# traduttore.net
KiCad netlist of a schematic drawn in EAGLE
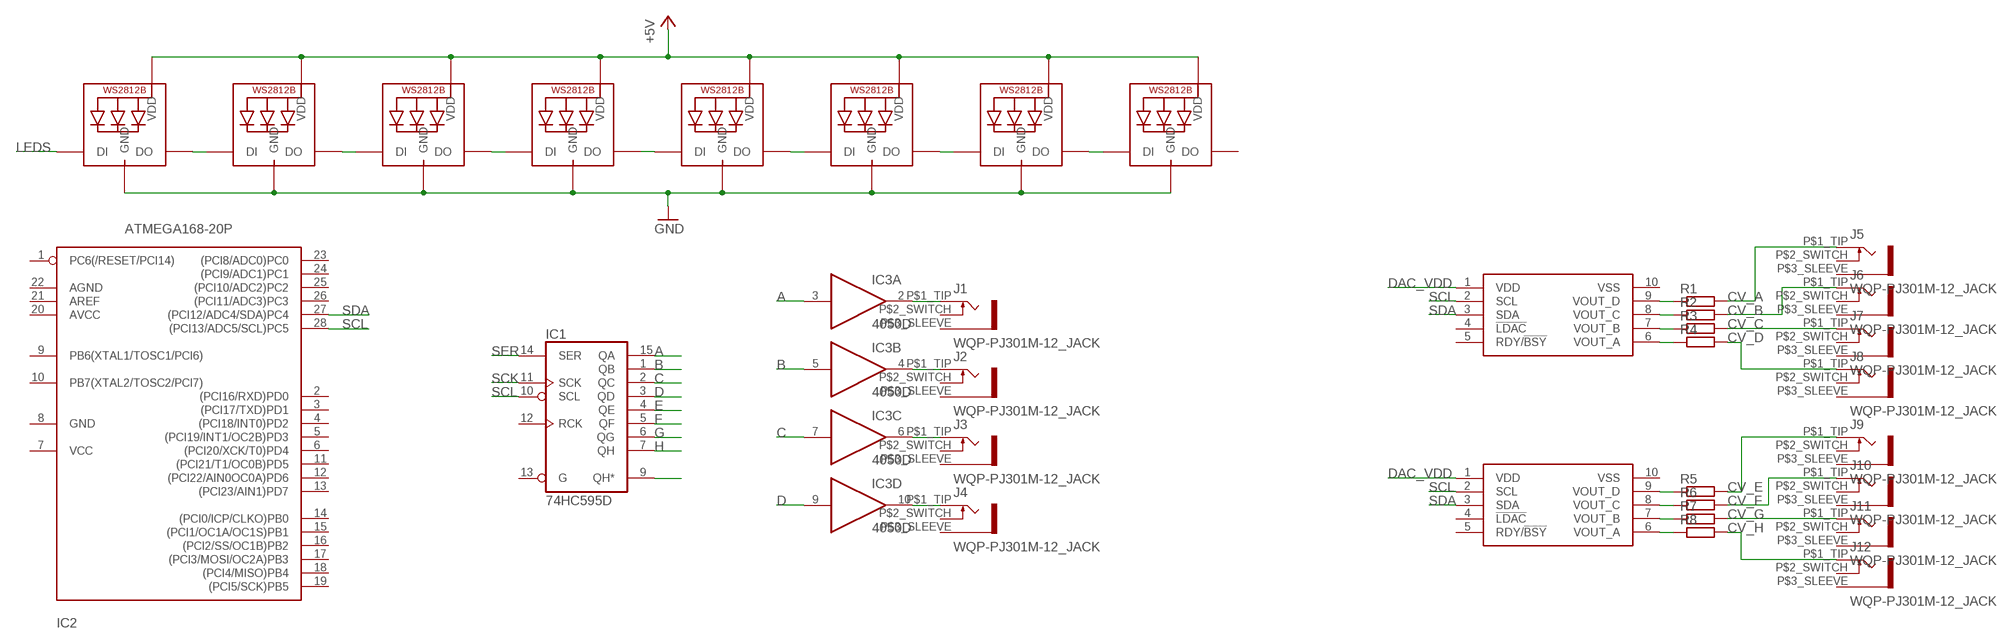
[diagram p0: schematic, sheet 1]

(export (version "E")
  (design (tool "Eeschema 10.0.6"))
  (components
    (comp (ref "IC1")
      (value "74HC595D")
      (footprint "eagle-import:SO16")
      (libsource (lib "eagle-import") (part "74595DHC"))
    )
    (comp (ref "IC2")
      (value "ATMEGA168-20P")
      (footprint "eagle-import:DIL28-3")
      (libsource (lib "eagle-import") (part "ATMEGA168P-20"))
    )
    (comp (ref "IC3")
      (value "4050D")
      (footprint "eagle-import:SO16")
      (libsource (lib "eagle-import") (part "4050D"))
    )
    (comp (ref "J1")
      (value "WQP-PJ301M-12_JACK")
      (footprint "eagle-import:WQP-PJ301M-12_JACK")
      (libsource (lib "eagle-import") (part "WQP-PJ301M-12_JACK"))
    )
    (comp (ref "J2")
      (value "WQP-PJ301M-12_JACK")
      (footprint "eagle-import:WQP-PJ301M-12_JACK")
      (libsource (lib "eagle-import") (part "WQP-PJ301M-12_JACK"))
    )
    (comp (ref "J3")
      (value "WQP-PJ301M-12_JACK")
      (footprint "eagle-import:WQP-PJ301M-12_JACK")
      (libsource (lib "eagle-import") (part "WQP-PJ301M-12_JACK"))
    )
    (comp (ref "J4")
      (value "WQP-PJ301M-12_JACK")
      (footprint "eagle-import:WQP-PJ301M-12_JACK")
      (libsource (lib "eagle-import") (part "WQP-PJ301M-12_JACK"))
    )
    (comp (ref "J5")
      (value "WQP-PJ301M-12_JACK")
      (footprint "eagle-import:WQP-PJ301M-12_JACK")
      (libsource (lib "eagle-import") (part "WQP-PJ301M-12_JACK"))
    )
    (comp (ref "J6")
      (value "WQP-PJ301M-12_JACK")
      (footprint "eagle-import:WQP-PJ301M-12_JACK")
      (libsource (lib "eagle-import") (part "WQP-PJ301M-12_JACK"))
    )
    (comp (ref "J7")
      (value "WQP-PJ301M-12_JACK")
      (footprint "eagle-import:WQP-PJ301M-12_JACK")
      (libsource (lib "eagle-import") (part "WQP-PJ301M-12_JACK"))
    )
    (comp (ref "J8")
      (value "WQP-PJ301M-12_JACK")
      (footprint "eagle-import:WQP-PJ301M-12_JACK")
      (libsource (lib "eagle-import") (part "WQP-PJ301M-12_JACK"))
    )
    (comp (ref "J9")
      (value "WQP-PJ301M-12_JACK")
      (footprint "eagle-import:WQP-PJ301M-12_JACK")
      (libsource (lib "eagle-import") (part "WQP-PJ301M-12_JACK"))
    )
    (comp (ref "J10")
      (value "WQP-PJ301M-12_JACK")
      (footprint "eagle-import:WQP-PJ301M-12_JACK")
      (libsource (lib "eagle-import") (part "WQP-PJ301M-12_JACK"))
    )
    (comp (ref "J11")
      (value "WQP-PJ301M-12_JACK")
      (footprint "eagle-import:WQP-PJ301M-12_JACK")
      (libsource (lib "eagle-import") (part "WQP-PJ301M-12_JACK"))
    )
    (comp (ref "J12")
      (value "WQP-PJ301M-12_JACK")
      (footprint "eagle-import:WQP-PJ301M-12_JACK")
      (libsource (lib "eagle-import") (part "WQP-PJ301M-12_JACK"))
    )
    (comp (ref "LED1")
      (value "WS2812B5050")
      (footprint "eagle-import:WS2812B")
      (libsource (lib "eagle-import") (part "WS2812B5050"))
    )
    (comp (ref "LED2")
      (value "WS2812B5050")
      (footprint "eagle-import:WS2812B")
      (libsource (lib "eagle-import") (part "WS2812B5050"))
    )
    (comp (ref "LED3")
      (value "WS2812B5050")
      (footprint "eagle-import:WS2812B")
      (libsource (lib "eagle-import") (part "WS2812B5050"))
    )
    (comp (ref "LED4")
      (value "WS2812B5050")
      (footprint "eagle-import:WS2812B")
      (libsource (lib "eagle-import") (part "WS2812B5050"))
    )
    (comp (ref "LED5")
      (value "WS2812B5050")
      (footprint "eagle-import:WS2812B")
      (libsource (lib "eagle-import") (part "WS2812B5050"))
    )
    (comp (ref "LED6")
      (value "WS2812B5050")
      (footprint "eagle-import:WS2812B")
      (libsource (lib "eagle-import") (part "WS2812B5050"))
    )
    (comp (ref "LED7")
      (value "WS2812B5050")
      (footprint "eagle-import:WS2812B")
      (libsource (lib "eagle-import") (part "WS2812B5050"))
    )
    (comp (ref "LED8")
      (value "WS2812B5050")
      (footprint "eagle-import:WS2812B")
      (libsource (lib "eagle-import") (part "WS2812B5050"))
    )
    (comp (ref "R1")
      (value "R-EU_R0805")
      (footprint "eagle-import:R0805")
      (libsource (lib "eagle-import") (part "R-EU_R0805"))
    )
    (comp (ref "R2")
      (value "R-EU_R0805")
      (footprint "eagle-import:R0805")
      (libsource (lib "eagle-import") (part "R-EU_R0805"))
    )
    (comp (ref "R3")
      (value "R-EU_R0805")
      (footprint "eagle-import:R0805")
      (libsource (lib "eagle-import") (part "R-EU_R0805"))
    )
    (comp (ref "R4")
      (value "R-EU_R0805")
      (footprint "eagle-import:R0805")
      (libsource (lib "eagle-import") (part "R-EU_R0805"))
    )
    (comp (ref "R5")
      (value "R-EU_R0805")
      (footprint "eagle-import:R0805")
      (libsource (lib "eagle-import") (part "R-EU_R0805"))
    )
    (comp (ref "R6")
      (value "R-EU_R0805")
      (footprint "eagle-import:R0805")
      (libsource (lib "eagle-import") (part "R-EU_R0805"))
    )
    (comp (ref "R7")
      (value "R-EU_R0805")
      (footprint "eagle-import:R0805")
      (libsource (lib "eagle-import") (part "R-EU_R0805"))
    )
    (comp (ref "R8")
      (value "R-EU_R0805")
      (footprint "eagle-import:R0805")
      (libsource (lib "eagle-import") (part "R-EU_R0805"))
    )
    (comp (ref "U$1")
      (value "MCP4728")
      (footprint "eagle-import:MSOP10")
      (libsource (lib "eagle-import") (part "MCP4728"))
    )
    (comp (ref "U$2")
      (value "MCP4728")
      (footprint "eagle-import:MSOP10")
      (libsource (lib "eagle-import") (part "MCP4728"))
    )
  )
  (nets
    (net (code "1") (name "+5V") (class "Default")
      (node (ref "LED1") (pin "1-VDD") (pinfunction "VDD_1-VDD") (pintype "power_in"))
      (node (ref "LED2") (pin "1-VDD") (pinfunction "VDD_1-VDD") (pintype "power_in"))
      (node (ref "LED3") (pin "1-VDD") (pinfunction "VDD_1-VDD") (pintype "power_in"))
      (node (ref "LED4") (pin "1-VDD") (pinfunction "VDD_1-VDD") (pintype "power_in"))
      (node (ref "LED5") (pin "1-VDD") (pinfunction "VDD_1-VDD") (pintype "power_in"))
      (node (ref "LED6") (pin "1-VDD") (pinfunction "VDD_1-VDD") (pintype "power_in"))
      (node (ref "LED7") (pin "1-VDD") (pinfunction "VDD_1-VDD") (pintype "power_in"))
      (node (ref "LED8") (pin "1-VDD") (pinfunction "VDD_1-VDD") (pintype "power_in"))
    )
    (net (code "2") (name "/A") (class "Default")
      (node (ref "IC1") (pin "15") (pinfunction "QA_15") (pintype "tri_state"))
      (node (ref "IC3") (pin "3") (pinfunction "I_3") (pintype "input"))
    )
    (net (code "3") (name "/B") (class "Default")
      (node (ref "IC1") (pin "1") (pinfunction "QB_1") (pintype "tri_state"))
      (node (ref "IC3") (pin "5") (pinfunction "I_5") (pintype "input"))
    )
    (net (code "4") (name "/C") (class "Default")
      (node (ref "IC1") (pin "2") (pinfunction "QC_2") (pintype "tri_state"))
      (node (ref "IC3") (pin "7") (pinfunction "I_7") (pintype "input"))
    )
    (net (code "5") (name "/CV_A") (class "Default")
      (node (ref "J5") (pin "P$1_TIP") (pinfunction "2_P$1_TIP") (pintype "passive"))
      (node (ref "R1") (pin "2") (pinfunction "2_2") (pintype "passive"))
    )
    (net (code "6") (name "/CV_B") (class "Default")
      (node (ref "J6") (pin "P$1_TIP") (pinfunction "2_P$1_TIP") (pintype "passive"))
      (node (ref "R2") (pin "2") (pinfunction "2_2") (pintype "passive"))
    )
    (net (code "7") (name "/CV_C") (class "Default")
      (node (ref "J7") (pin "P$1_TIP") (pinfunction "2_P$1_TIP") (pintype "passive"))
      (node (ref "R3") (pin "2") (pinfunction "2_2") (pintype "passive"))
    )
    (net (code "8") (name "/CV_D") (class "Default")
      (node (ref "J8") (pin "P$1_TIP") (pinfunction "2_P$1_TIP") (pintype "passive"))
      (node (ref "R4") (pin "2") (pinfunction "2_2") (pintype "passive"))
    )
    (net (code "9") (name "/CV_E") (class "Default")
      (node (ref "J9") (pin "P$1_TIP") (pinfunction "2_P$1_TIP") (pintype "passive"))
      (node (ref "R5") (pin "2") (pinfunction "2_2") (pintype "passive"))
    )
    (net (code "10") (name "/CV_F") (class "Default")
      (node (ref "J10") (pin "P$1_TIP") (pinfunction "2_P$1_TIP") (pintype "passive"))
      (node (ref "R6") (pin "2") (pinfunction "2_2") (pintype "passive"))
    )
    (net (code "11") (name "/CV_G") (class "Default")
      (node (ref "J11") (pin "P$1_TIP") (pinfunction "2_P$1_TIP") (pintype "passive"))
      (node (ref "R7") (pin "2") (pinfunction "2_2") (pintype "passive"))
    )
    (net (code "12") (name "/CV_H") (class "Default")
      (node (ref "J12") (pin "P$1_TIP") (pinfunction "2_P$1_TIP") (pintype "passive"))
      (node (ref "R8") (pin "2") (pinfunction "2_2") (pintype "passive"))
    )
    (net (code "13") (name "/D") (class "Default")
      (node (ref "IC1") (pin "3") (pinfunction "QD_3") (pintype "tri_state"))
      (node (ref "IC3") (pin "9") (pinfunction "I_9") (pintype "input"))
    )
    (net (code "14") (name "/DAC_VDD") (class "Default")
      (node (ref "U$1") (pin "1") (pinfunction "VDD_1") (pintype "bidirectional"))
      (node (ref "U$2") (pin "1") (pinfunction "VDD_1") (pintype "bidirectional"))
    )
    (net (code "15") (name "/E") (class "Default")
      (node (ref "IC1") (pin "4") (pinfunction "QE_4") (pintype "tri_state"))
    )
    (net (code "16") (name "/F") (class "Default")
      (node (ref "IC1") (pin "5") (pinfunction "QF_5") (pintype "tri_state"))
    )
    (net (code "17") (name "/G") (class "Default")
      (node (ref "IC1") (pin "6") (pinfunction "QG_6") (pintype "tri_state"))
    )
    (net (code "18") (name "/H") (class "Default")
      (node (ref "IC1") (pin "7") (pinfunction "QH_7") (pintype "tri_state"))
    )
    (net (code "19") (name "/LEDS") (class "Default")
      (node (ref "LED1") (pin "4-DIN") (pinfunction "DI_4-DIN") (pintype "input"))
    )
    (net (code "20") (name "/SCK") (class "Default")
      (node (ref "IC1") (pin "11") (pinfunction "SCK_11") (pintype "input"))
    )
    (net (code "21") (name "/SCL") (class "Default")
      (node (ref "IC1") (pin "10") (pinfunction "SCL_10") (pintype "input"))
      (node (ref "IC2") (pin "28") (pinfunction "(PCI13/ADC5/SCL)PC5_28") (pintype "bidirectional"))
      (node (ref "U$1") (pin "2") (pinfunction "SCL_2") (pintype "bidirectional"))
      (node (ref "U$2") (pin "2") (pinfunction "SCL_2") (pintype "bidirectional"))
    )
    (net (code "22") (name "/SDA") (class "Default")
      (node (ref "IC2") (pin "27") (pinfunction "(PCI12/ADC4/SDA)PC4_27") (pintype "bidirectional"))
      (node (ref "U$1") (pin "3") (pinfunction "SDA_3") (pintype "bidirectional"))
      (node (ref "U$2") (pin "3") (pinfunction "SDA_3") (pintype "bidirectional"))
    )
    (net (code "23") (name "/SER") (class "Default")
      (node (ref "IC1") (pin "14") (pinfunction "SER_14") (pintype "input"))
    )
    (net (code "24") (name "GND") (class "Default")
      (node (ref "LED1") (pin "3-GND") (pinfunction "GND_3-GND") (pintype "power_in"))
      (node (ref "LED2") (pin "3-GND") (pinfunction "GND_3-GND") (pintype "power_in"))
      (node (ref "LED3") (pin "3-GND") (pinfunction "GND_3-GND") (pintype "power_in"))
      (node (ref "LED4") (pin "3-GND") (pinfunction "GND_3-GND") (pintype "power_in"))
      (node (ref "LED5") (pin "3-GND") (pinfunction "GND_3-GND") (pintype "power_in"))
      (node (ref "LED6") (pin "3-GND") (pinfunction "GND_3-GND") (pintype "power_in"))
      (node (ref "LED7") (pin "3-GND") (pinfunction "GND_3-GND") (pintype "power_in"))
      (node (ref "LED8") (pin "3-GND") (pinfunction "GND_3-GND") (pintype "power_in"))
    )
    (net (code "25") (name "Net-(IC3A-O)") (class "Default")
      (node (ref "IC3") (pin "2") (pinfunction "O_2") (pintype "output"))
      (node (ref "J1") (pin "P$1_TIP") (pinfunction "2_P$1_TIP") (pintype "passive"))
    )
    (net (code "26") (name "Net-(IC3B-O)") (class "Default")
      (node (ref "IC3") (pin "4") (pinfunction "O_4") (pintype "output"))
      (node (ref "J2") (pin "P$1_TIP") (pinfunction "2_P$1_TIP") (pintype "passive"))
    )
    (net (code "27") (name "Net-(IC3C-O)") (class "Default")
      (node (ref "IC3") (pin "6") (pinfunction "O_6") (pintype "output"))
      (node (ref "J3") (pin "P$1_TIP") (pinfunction "2_P$1_TIP") (pintype "passive"))
    )
    (net (code "28") (name "Net-(IC3D-O)") (class "Default")
      (node (ref "IC3") (pin "10") (pinfunction "O_10") (pintype "output"))
      (node (ref "J4") (pin "P$1_TIP") (pinfunction "2_P$1_TIP") (pintype "passive"))
    )
    (net (code "29") (name "Net-(LED1-DO)") (class "Default")
      (node (ref "LED1") (pin "2-DOUT") (pinfunction "DO_2-DOUT") (pintype "output"))
      (node (ref "LED2") (pin "4-DIN") (pinfunction "DI_4-DIN") (pintype "input"))
    )
    (net (code "30") (name "Net-(LED2-DO)") (class "Default")
      (node (ref "LED2") (pin "2-DOUT") (pinfunction "DO_2-DOUT") (pintype "output"))
      (node (ref "LED3") (pin "4-DIN") (pinfunction "DI_4-DIN") (pintype "input"))
    )
    (net (code "31") (name "Net-(LED3-DO)") (class "Default")
      (node (ref "LED3") (pin "2-DOUT") (pinfunction "DO_2-DOUT") (pintype "output"))
      (node (ref "LED4") (pin "4-DIN") (pinfunction "DI_4-DIN") (pintype "input"))
    )
    (net (code "32") (name "Net-(LED4-DO)") (class "Default")
      (node (ref "LED4") (pin "2-DOUT") (pinfunction "DO_2-DOUT") (pintype "output"))
      (node (ref "LED5") (pin "4-DIN") (pinfunction "DI_4-DIN") (pintype "input"))
    )
    (net (code "33") (name "Net-(LED5-DO)") (class "Default")
      (node (ref "LED5") (pin "2-DOUT") (pinfunction "DO_2-DOUT") (pintype "output"))
      (node (ref "LED6") (pin "4-DIN") (pinfunction "DI_4-DIN") (pintype "input"))
    )
    (net (code "34") (name "Net-(LED6-DO)") (class "Default")
      (node (ref "LED6") (pin "2-DOUT") (pinfunction "DO_2-DOUT") (pintype "output"))
      (node (ref "LED7") (pin "4-DIN") (pinfunction "DI_4-DIN") (pintype "input"))
    )
    (net (code "35") (name "Net-(LED7-DO)") (class "Default")
      (node (ref "LED7") (pin "2-DOUT") (pinfunction "DO_2-DOUT") (pintype "output"))
      (node (ref "LED8") (pin "4-DIN") (pinfunction "DI_4-DIN") (pintype "input"))
    )
    (net (code "36") (name "Net-(U$1-VOUT_A)") (class "Default")
      (node (ref "R4") (pin "1") (pinfunction "1_1") (pintype "passive"))
      (node (ref "U$1") (pin "6") (pinfunction "VOUT_A_6") (pintype "bidirectional"))
    )
    (net (code "37") (name "Net-(U$1-VOUT_B)") (class "Default")
      (node (ref "R3") (pin "1") (pinfunction "1_1") (pintype "passive"))
      (node (ref "U$1") (pin "7") (pinfunction "VOUT_B_7") (pintype "bidirectional"))
    )
    (net (code "38") (name "Net-(U$1-VOUT_C)") (class "Default")
      (node (ref "R2") (pin "1") (pinfunction "1_1") (pintype "passive"))
      (node (ref "U$1") (pin "8") (pinfunction "VOUT_C_8") (pintype "bidirectional"))
    )
    (net (code "39") (name "Net-(U$1-VOUT_D)") (class "Default")
      (node (ref "R1") (pin "1") (pinfunction "1_1") (pintype "passive"))
      (node (ref "U$1") (pin "9") (pinfunction "VOUT_D_9") (pintype "bidirectional"))
    )
    (net (code "40") (name "Net-(U$2-VOUT_A)") (class "Default")
      (node (ref "R8") (pin "1") (pinfunction "1_1") (pintype "passive"))
      (node (ref "U$2") (pin "6") (pinfunction "VOUT_A_6") (pintype "bidirectional"))
    )
    (net (code "41") (name "Net-(U$2-VOUT_B)") (class "Default")
      (node (ref "R7") (pin "1") (pinfunction "1_1") (pintype "passive"))
      (node (ref "U$2") (pin "7") (pinfunction "VOUT_B_7") (pintype "bidirectional"))
    )
    (net (code "42") (name "Net-(U$2-VOUT_C)") (class "Default")
      (node (ref "R6") (pin "1") (pinfunction "1_1") (pintype "passive"))
      (node (ref "U$2") (pin "8") (pinfunction "VOUT_C_8") (pintype "bidirectional"))
    )
    (net (code "43") (name "Net-(U$2-VOUT_D)") (class "Default")
      (node (ref "R5") (pin "1") (pinfunction "1_1") (pintype "passive"))
      (node (ref "U$2") (pin "9") (pinfunction "VOUT_D_9") (pintype "bidirectional"))
    )
    (net (code "44") (name "unconnected-(IC1A-G-Pad13)") (class "Default")
      (node (ref "IC1") (pin "13") (pinfunction "G_13") (pintype "input"))
    )
    (net (code "45") (name "unconnected-(IC1A-QH*-Pad9)") (class "Default")
      (node (ref "IC1") (pin "9") (pinfunction "QH*_9") (pintype "tri_state"))
    )
    (net (code "46") (name "unconnected-(IC1A-RCK-Pad12)") (class "Default")
      (node (ref "IC1") (pin "12") (pinfunction "RCK_12") (pintype "input"))
    )
    (net (code "47") (name "unconnected-(IC2-(PCI0{slash}ICP{slash}CLKO)PB0-Pad14)") (class "Default")
      (node (ref "IC2") (pin "14") (pinfunction "(PCI0/ICP/CLKO)PB0_14") (pintype "bidirectional"))
    )
    (net (code "48") (name "unconnected-(IC2-(PCI1{slash}OC1A{slash}OC1S)PB1-Pad15)") (class "Default")
      (node (ref "IC2") (pin "15") (pinfunction "(PCI1/OC1A/OC1S)PB1_15") (pintype "bidirectional"))
    )
    (net (code "49") (name "unconnected-(IC2-(PCI2{slash}SS{slash}OC1B)PB2-Pad16)") (class "Default")
      (node (ref "IC2") (pin "16") (pinfunction "(PCI2/SS/OC1B)PB2_16") (pintype "bidirectional"))
    )
    (net (code "50") (name "unconnected-(IC2-(PCI3{slash}MOSI{slash}OC2A)PB3-Pad17)") (class "Default")
      (node (ref "IC2") (pin "17") (pinfunction "(PCI3/MOSI/OC2A)PB3_17") (pintype "bidirectional"))
    )
    (net (code "51") (name "unconnected-(IC2-(PCI4{slash}MISO)PB4-Pad18)") (class "Default")
      (node (ref "IC2") (pin "18") (pinfunction "(PCI4/MISO)PB4_18") (pintype "bidirectional"))
    )
    (net (code "52") (name "unconnected-(IC2-(PCI5{slash}SCK)PB5-Pad19)") (class "Default")
      (node (ref "IC2") (pin "19") (pinfunction "(PCI5/SCK)PB5_19") (pintype "bidirectional"))
    )
    (net (code "53") (name "unconnected-(IC2-(PCI8{slash}ADC0)PC0-Pad23)") (class "Default")
      (node (ref "IC2") (pin "23") (pinfunction "(PCI8/ADC0)PC0_23") (pintype "bidirectional"))
    )
    (net (code "54") (name "unconnected-(IC2-(PCI9{slash}ADC1)PC1-Pad24)") (class "Default")
      (node (ref "IC2") (pin "24") (pinfunction "(PCI9/ADC1)PC1_24") (pintype "bidirectional"))
    )
    (net (code "55") (name "unconnected-(IC2-(PCI10{slash}ADC2)PC2-Pad25)") (class "Default")
      (node (ref "IC2") (pin "25") (pinfunction "(PCI10/ADC2)PC2_25") (pintype "bidirectional"))
    )
    (net (code "56") (name "unconnected-(IC2-(PCI11{slash}ADC3)PC3-Pad26)") (class "Default")
      (node (ref "IC2") (pin "26") (pinfunction "(PCI11/ADC3)PC3_26") (pintype "bidirectional"))
    )
    (net (code "57") (name "unconnected-(IC2-(PCI16{slash}RXD)PD0-Pad2)") (class "Default")
      (node (ref "IC2") (pin "2") (pinfunction "(PCI16/RXD)PD0_2") (pintype "bidirectional"))
    )
    (net (code "58") (name "unconnected-(IC2-(PCI17{slash}TXD)PD1-Pad3)") (class "Default")
      (node (ref "IC2") (pin "3") (pinfunction "(PCI17/TXD)PD1_3") (pintype "bidirectional"))
    )
    (net (code "59") (name "unconnected-(IC2-(PCI18{slash}INT0)PD2-Pad4)") (class "Default")
      (node (ref "IC2") (pin "4") (pinfunction "(PCI18/INT0)PD2_4") (pintype "bidirectional"))
    )
    (net (code "60") (name "unconnected-(IC2-(PCI19{slash}INT1{slash}OC2B)PD3-Pad5)") (class "Default")
      (node (ref "IC2") (pin "5") (pinfunction "(PCI19/INT1/OC2B)PD3_5") (pintype "bidirectional"))
    )
    (net (code "61") (name "unconnected-(IC2-(PCI20{slash}XCK{slash}T0)PD4-Pad6)") (class "Default")
      (node (ref "IC2") (pin "6") (pinfunction "(PCI20/XCK/T0)PD4_6") (pintype "bidirectional"))
    )
    (net (code "62") (name "unconnected-(IC2-(PCI21{slash}T1{slash}OC0B)PD5-Pad11)") (class "Default")
      (node (ref "IC2") (pin "11") (pinfunction "(PCI21/T1/OC0B)PD5_11") (pintype "bidirectional"))
    )
    (net (code "63") (name "unconnected-(IC2-(PCI22{slash}AIN0OC0A)PD6-Pad12)") (class "Default")
      (node (ref "IC2") (pin "12") (pinfunction "(PCI22/AIN0OC0A)PD6_12") (pintype "bidirectional"))
    )
    (net (code "64") (name "unconnected-(IC2-(PCI23{slash}AIN1)PD7-Pad13)") (class "Default")
      (node (ref "IC2") (pin "13") (pinfunction "(PCI23/AIN1)PD7_13") (pintype "bidirectional"))
    )
    (net (code "65") (name "unconnected-(IC2-AGND-Pad22)") (class "Default")
      (node (ref "IC2") (pin "22") (pinfunction "AGND_22") (pintype "bidirectional"))
    )
    (net (code "66") (name "unconnected-(IC2-AREF-Pad21)") (class "Default")
      (node (ref "IC2") (pin "21") (pinfunction "AREF_21") (pintype "bidirectional"))
    )
    (net (code "67") (name "unconnected-(IC2-AVCC-Pad20)") (class "Default")
      (node (ref "IC2") (pin "20") (pinfunction "AVCC_20") (pintype "bidirectional"))
    )
    (net (code "68") (name "unconnected-(IC2-GND-Pad8)") (class "Default")
      (node (ref "IC2") (pin "8") (pinfunction "GND_8") (pintype "bidirectional"))
    )
    (net (code "69") (name "unconnected-(IC2-PB6(XTAL1{slash}TOSC1{slash}PCI6)-Pad9)") (class "Default")
      (node (ref "IC2") (pin "9") (pinfunction "PB6(XTAL1/TOSC1/PCI6)_9") (pintype "bidirectional"))
    )
    (net (code "70") (name "unconnected-(IC2-PB7(XTAL2{slash}TOSC2{slash}PCI7)-Pad10)") (class "Default")
      (node (ref "IC2") (pin "10") (pinfunction "PB7(XTAL2/TOSC2/PCI7)_10") (pintype "bidirectional"))
    )
    (net (code "71") (name "unconnected-(IC2-PC6({slash}RESET{slash}PCI14)-Pad1)") (class "Default")
      (node (ref "IC2") (pin "1") (pinfunction "PC6(/RESET/PCI14)_1") (pintype "bidirectional"))
    )
    (net (code "72") (name "unconnected-(IC2-VCC-Pad7)") (class "Default")
      (node (ref "IC2") (pin "7") (pinfunction "VCC_7") (pintype "bidirectional"))
    )
    (net (code "73") (name "unconnected-(J1-1-PadP$3_SLEEVE)") (class "Default")
      (node (ref "J1") (pin "P$3_SLEEVE") (pinfunction "1_P$3_SLEEVE") (pintype "passive"))
    )
    (net (code "74") (name "unconnected-(J1-3-PadP$2_SWITCH)") (class "Default")
      (node (ref "J1") (pin "P$2_SWITCH") (pinfunction "3_P$2_SWITCH") (pintype "passive"))
    )
    (net (code "75") (name "unconnected-(J2-1-PadP$3_SLEEVE)") (class "Default")
      (node (ref "J2") (pin "P$3_SLEEVE") (pinfunction "1_P$3_SLEEVE") (pintype "passive"))
    )
    (net (code "76") (name "unconnected-(J2-3-PadP$2_SWITCH)") (class "Default")
      (node (ref "J2") (pin "P$2_SWITCH") (pinfunction "3_P$2_SWITCH") (pintype "passive"))
    )
    (net (code "77") (name "unconnected-(J3-1-PadP$3_SLEEVE)") (class "Default")
      (node (ref "J3") (pin "P$3_SLEEVE") (pinfunction "1_P$3_SLEEVE") (pintype "passive"))
    )
    (net (code "78") (name "unconnected-(J3-3-PadP$2_SWITCH)") (class "Default")
      (node (ref "J3") (pin "P$2_SWITCH") (pinfunction "3_P$2_SWITCH") (pintype "passive"))
    )
    (net (code "79") (name "unconnected-(J4-1-PadP$3_SLEEVE)") (class "Default")
      (node (ref "J4") (pin "P$3_SLEEVE") (pinfunction "1_P$3_SLEEVE") (pintype "passive"))
    )
    (net (code "80") (name "unconnected-(J4-3-PadP$2_SWITCH)") (class "Default")
      (node (ref "J4") (pin "P$2_SWITCH") (pinfunction "3_P$2_SWITCH") (pintype "passive"))
    )
    (net (code "81") (name "unconnected-(J5-1-PadP$3_SLEEVE)") (class "Default")
      (node (ref "J5") (pin "P$3_SLEEVE") (pinfunction "1_P$3_SLEEVE") (pintype "passive"))
    )
    (net (code "82") (name "unconnected-(J5-3-PadP$2_SWITCH)") (class "Default")
      (node (ref "J5") (pin "P$2_SWITCH") (pinfunction "3_P$2_SWITCH") (pintype "passive"))
    )
    (net (code "83") (name "unconnected-(J6-1-PadP$3_SLEEVE)") (class "Default")
      (node (ref "J6") (pin "P$3_SLEEVE") (pinfunction "1_P$3_SLEEVE") (pintype "passive"))
    )
    (net (code "84") (name "unconnected-(J6-3-PadP$2_SWITCH)") (class "Default")
      (node (ref "J6") (pin "P$2_SWITCH") (pinfunction "3_P$2_SWITCH") (pintype "passive"))
    )
    (net (code "85") (name "unconnected-(J7-1-PadP$3_SLEEVE)") (class "Default")
      (node (ref "J7") (pin "P$3_SLEEVE") (pinfunction "1_P$3_SLEEVE") (pintype "passive"))
    )
    (net (code "86") (name "unconnected-(J7-3-PadP$2_SWITCH)") (class "Default")
      (node (ref "J7") (pin "P$2_SWITCH") (pinfunction "3_P$2_SWITCH") (pintype "passive"))
    )
    (net (code "87") (name "unconnected-(J8-1-PadP$3_SLEEVE)") (class "Default")
      (node (ref "J8") (pin "P$3_SLEEVE") (pinfunction "1_P$3_SLEEVE") (pintype "passive"))
    )
    (net (code "88") (name "unconnected-(J8-3-PadP$2_SWITCH)") (class "Default")
      (node (ref "J8") (pin "P$2_SWITCH") (pinfunction "3_P$2_SWITCH") (pintype "passive"))
    )
    (net (code "89") (name "unconnected-(J9-1-PadP$3_SLEEVE)") (class "Default")
      (node (ref "J9") (pin "P$3_SLEEVE") (pinfunction "1_P$3_SLEEVE") (pintype "passive"))
    )
    (net (code "90") (name "unconnected-(J9-3-PadP$2_SWITCH)") (class "Default")
      (node (ref "J9") (pin "P$2_SWITCH") (pinfunction "3_P$2_SWITCH") (pintype "passive"))
    )
    (net (code "91") (name "unconnected-(J10-1-PadP$3_SLEEVE)") (class "Default")
      (node (ref "J10") (pin "P$3_SLEEVE") (pinfunction "1_P$3_SLEEVE") (pintype "passive"))
    )
    (net (code "92") (name "unconnected-(J10-3-PadP$2_SWITCH)") (class "Default")
      (node (ref "J10") (pin "P$2_SWITCH") (pinfunction "3_P$2_SWITCH") (pintype "passive"))
    )
    (net (code "93") (name "unconnected-(J11-1-PadP$3_SLEEVE)") (class "Default")
      (node (ref "J11") (pin "P$3_SLEEVE") (pinfunction "1_P$3_SLEEVE") (pintype "passive"))
    )
    (net (code "94") (name "unconnected-(J11-3-PadP$2_SWITCH)") (class "Default")
      (node (ref "J11") (pin "P$2_SWITCH") (pinfunction "3_P$2_SWITCH") (pintype "passive"))
    )
    (net (code "95") (name "unconnected-(J12-1-PadP$3_SLEEVE)") (class "Default")
      (node (ref "J12") (pin "P$3_SLEEVE") (pinfunction "1_P$3_SLEEVE") (pintype "passive"))
    )
    (net (code "96") (name "unconnected-(J12-3-PadP$2_SWITCH)") (class "Default")
      (node (ref "J12") (pin "P$2_SWITCH") (pinfunction "3_P$2_SWITCH") (pintype "passive"))
    )
    (net (code "97") (name "unconnected-(LED8-DO-Pad2-DOUT)") (class "Default")
      (node (ref "LED8") (pin "2-DOUT") (pinfunction "DO_2-DOUT") (pintype "output"))
    )
    (net (code "98") (name "unconnected-(U$1-RDY{slash}~{BSY}-Pad5)") (class "Default")
      (node (ref "U$1") (pin "5") (pinfunction "RDY/~{BSY}_5") (pintype "bidirectional"))
    )
    (net (code "99") (name "unconnected-(U$1-VSS-Pad10)") (class "Default")
      (node (ref "U$1") (pin "10") (pinfunction "VSS_10") (pintype "bidirectional"))
    )
    (net (code "100") (name "unconnected-(U$1-~{LDAC}-Pad4)") (class "Default")
      (node (ref "U$1") (pin "4") (pinfunction "~{LDAC}_4") (pintype "bidirectional"))
    )
    (net (code "101") (name "unconnected-(U$2-RDY{slash}~{BSY}-Pad5)") (class "Default")
      (node (ref "U$2") (pin "5") (pinfunction "RDY/~{BSY}_5") (pintype "bidirectional"))
    )
    (net (code "102") (name "unconnected-(U$2-VSS-Pad10)") (class "Default")
      (node (ref "U$2") (pin "10") (pinfunction "VSS_10") (pintype "bidirectional"))
    )
    (net (code "103") (name "unconnected-(U$2-~{LDAC}-Pad4)") (class "Default")
      (node (ref "U$2") (pin "4") (pinfunction "~{LDAC}_4") (pintype "bidirectional"))
    )
  )
)
